# v1_0.net
KiCad netlist of a schematic drawn in Altium Designer
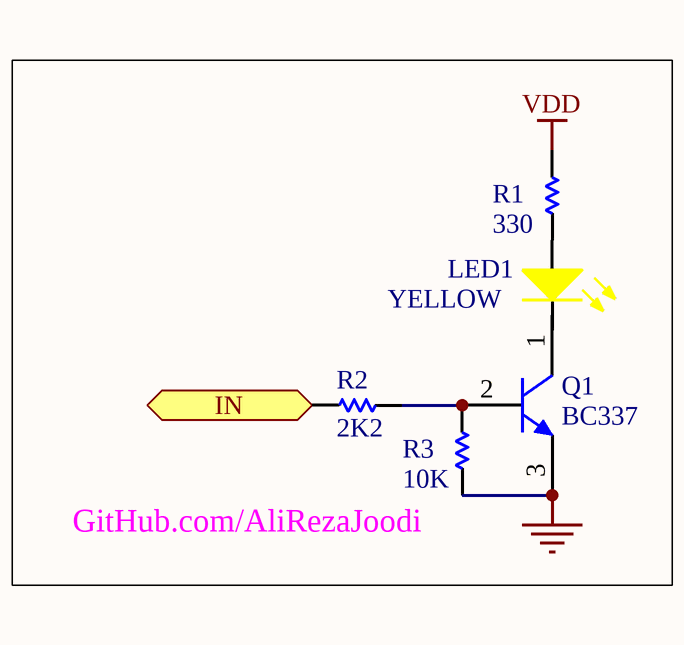
[diagram p0: v1.0.SchDoc]

(export (version "E")
  (design (tool "Eeschema 10.0.6"))
  (components
    (comp (ref "LED1")
      (value "YELLOW")
      (footprint "LED_THD_3MM_YELLOW_R")
      (description "LED, Yellow")
      (fields (field (name "MANUFACTURER") "Generic Components") (field (name "PUBLISHER") "Altium Limited"))
      (libsource (lib "Display") (part "LED_YELLOW"))
    )
    (comp (ref "Q1")
      (value "BC337")
      (footprint "TO92_3Pin_Form3")
      (description "Transistor, BJT, NPN")
      (libsource (lib "General") (part "Transistor_BJT_NPN"))
    )
    (comp (ref "R1")
      (value "330")
      (footprint "R_THD_AXIAL0.4(1/4W)")
      (description "Resistor")
      (libsource (lib "General") (part "Resistor"))
    )
    (comp (ref "R2")
      (value "2K2")
      (footprint "R_THD_AXIAL0.4(1/4W)")
      (description "Resistor")
      (libsource (lib "General") (part "Resistor"))
    )
    (comp (ref "R3")
      (value "10K")
      (footprint "R_THD_AXIAL0.4(1/4W)")
      (description "Resistor")
      (libsource (lib "General") (part "Resistor"))
    )
  )
  (nets
    (net (code "1") (name "/IN") (class "Default")
      (node (ref "R2") (pin "1") (pinfunction "1_1") (pintype "passive"))
    )
    (net (code "2") (name "GND") (class "Default")
      (node (ref "Q1") (pin "3") (pinfunction "E_3") (pintype "passive"))
      (node (ref "R3") (pin "1") (pinfunction "1_1") (pintype "passive"))
    )
    (net (code "3") (name "Net-(LED1-A)") (class "Default")
      (node (ref "LED1") (pin "1") (pinfunction "A_1") (pintype "passive"))
      (node (ref "R1") (pin "1") (pinfunction "1_1") (pintype "passive"))
    )
    (net (code "4") (name "Net-(Q1-B)") (class "Default")
      (node (ref "Q1") (pin "2") (pinfunction "B_2") (pintype "passive"))
      (node (ref "R2") (pin "2") (pinfunction "2_2") (pintype "passive"))
      (node (ref "R3") (pin "2") (pinfunction "2_2") (pintype "passive"))
    )
    (net (code "5") (name "VDD") (class "Default")
      (node (ref "R1") (pin "2") (pinfunction "2_2") (pintype "passive"))
    )
    (net (code "6") (name "unconnected-(LED1-K-Pad2)") (class "Default")
      (node (ref "LED1") (pin "2") (pinfunction "K_2") (pintype "passive"))
    )
    (net (code "7") (name "unconnected-(Q1-C-Pad1)") (class "Default")
      (node (ref "Q1") (pin "1") (pinfunction "C_1") (pintype "passive"))
    )
  )
)
